# USBC.net
KiCad netlist of a schematic drawn in Altium Designer
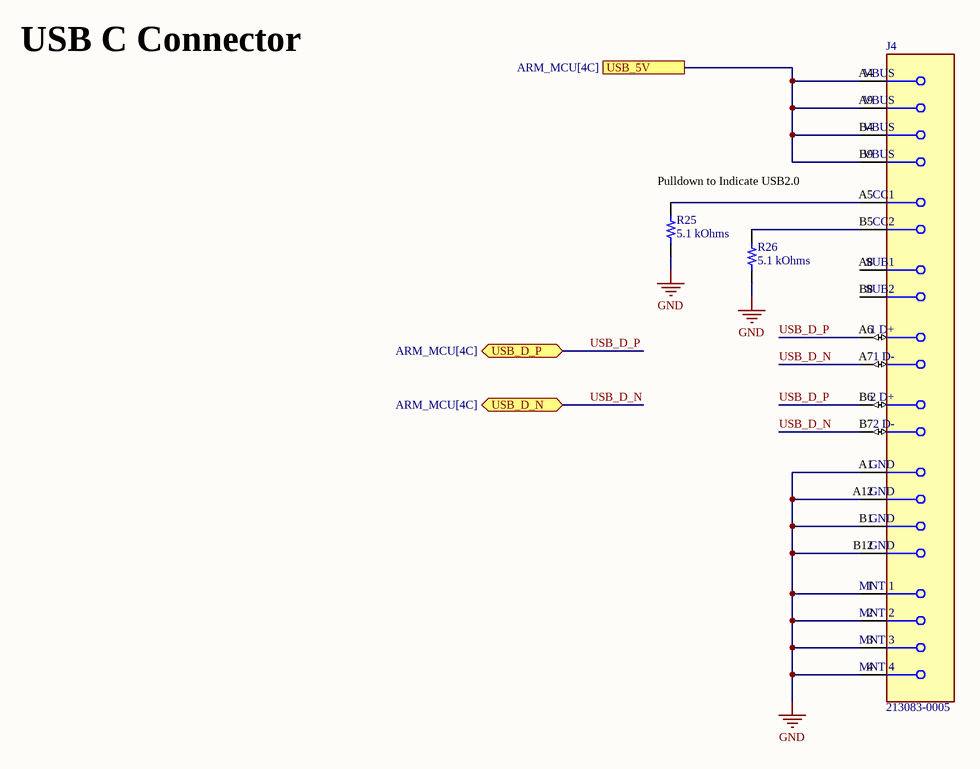
[diagram p0: USBC.SchDoc]

(export (version "E")
  (design (tool "Eeschema 10.0.6"))
  (components
    (comp (ref "J4")
      (value "213083-0005")
      (footprint "FP-2130830005-MFG")
      (description "CONN RCP USB2.0 TYP C 24P SMD RA")
      (libsource (lib "Altium Content Vault") (part "19c02d2f2bfb43c17c60460c929b15b"))
    )
    (comp (ref "R25")
      (value "5.1 kOhms")
      (footprint "RES 0603_1608")
      (description "RES 5.1K OHM 0.1% 1/10W 0603")
      (fields (field (name "PART NUMBER") "TNPW06035K10BYEN") (field (name "MANUFACTURER") "Vishay Dale"))
      (libsource (lib "Celestial Altium Library - altium_library") (part "Resistor"))
    )
    (comp (ref "R26")
      (value "5.1 kOhms")
      (footprint "RES 0603_1608")
      (description "RES 5.1K OHM 0.1% 1/10W 0603")
      (fields (field (name "PART NUMBER") "TNPW06035K10BYEN") (field (name "MANUFACTURER") "Vishay Dale"))
      (libsource (lib "Celestial Altium Library - altium_library") (part "Resistor"))
    )
  )
  (nets
    (net (code "1") (name "/USB_5V") (class "Default")
      (node (ref "J4") (pin "A4") (pinfunction "VBUS_A4") (pintype "power_in"))
      (node (ref "J4") (pin "A9") (pinfunction "VBUS_A9") (pintype "power_in"))
      (node (ref "J4") (pin "B4") (pinfunction "VBUS_B4") (pintype "power_in"))
      (node (ref "J4") (pin "B9") (pinfunction "VBUS_B9") (pintype "power_in"))
    )
    (net (code "2") (name "/USB_D_N") (class "Default")
      (node (ref "J4") (pin "A7") (pinfunction "1_D-_A7") (pintype "bidirectional"))
      (node (ref "J4") (pin "B7") (pinfunction "2_D-_B7") (pintype "bidirectional"))
    )
    (net (code "3") (name "/USB_D_P") (class "Default")
      (node (ref "J4") (pin "A6") (pinfunction "1_D+_A6") (pintype "bidirectional"))
      (node (ref "J4") (pin "B6") (pinfunction "2_D+_B6") (pintype "bidirectional"))
    )
    (net (code "4") (name "GND") (class "Default")
      (node (ref "J4") (pin "1") (pinfunction "MNT_1_1") (pintype "passive"))
      (node (ref "J4") (pin "2") (pinfunction "MNT_2_2") (pintype "passive"))
      (node (ref "J4") (pin "3") (pinfunction "MNT_3_3") (pintype "passive"))
      (node (ref "J4") (pin "4") (pinfunction "MNT_4_4") (pintype "passive"))
      (node (ref "J4") (pin "A1") (pinfunction "GND_A1") (pintype "power_in"))
      (node (ref "J4") (pin "A12") (pinfunction "GND_A12") (pintype "power_in"))
      (node (ref "J4") (pin "B1") (pinfunction "GND_B1") (pintype "power_in"))
      (node (ref "J4") (pin "B12") (pinfunction "GND_B12") (pintype "power_in"))
      (node (ref "R25") (pin "1") (pinfunction "1_1") (pintype "passive"))
      (node (ref "R26") (pin "1") (pinfunction "1_1") (pintype "passive"))
    )
    (net (code "5") (name "Net-(J4-CC1)") (class "Default")
      (node (ref "J4") (pin "A5") (pinfunction "CC1_A5") (pintype "passive"))
      (node (ref "R25") (pin "2") (pinfunction "2_2") (pintype "passive"))
    )
    (net (code "6") (name "Net-(J4-CC2)") (class "Default")
      (node (ref "J4") (pin "B5") (pinfunction "CC2_B5") (pintype "passive"))
      (node (ref "R26") (pin "2") (pinfunction "2_2") (pintype "passive"))
    )
    (net (code "7") (name "unconnected-(J4-SUB1-PadA8)") (class "Default")
      (node (ref "J4") (pin "A8") (pinfunction "SUB1_A8") (pintype "passive"))
    )
    (net (code "8") (name "unconnected-(J4-SUB2-PadB8)") (class "Default")
      (node (ref "J4") (pin "B8") (pinfunction "SUB2_B8") (pintype "passive"))
    )
  )
)
